# esplash.net
KiCad netlist of a schematic drawn in EAGLE
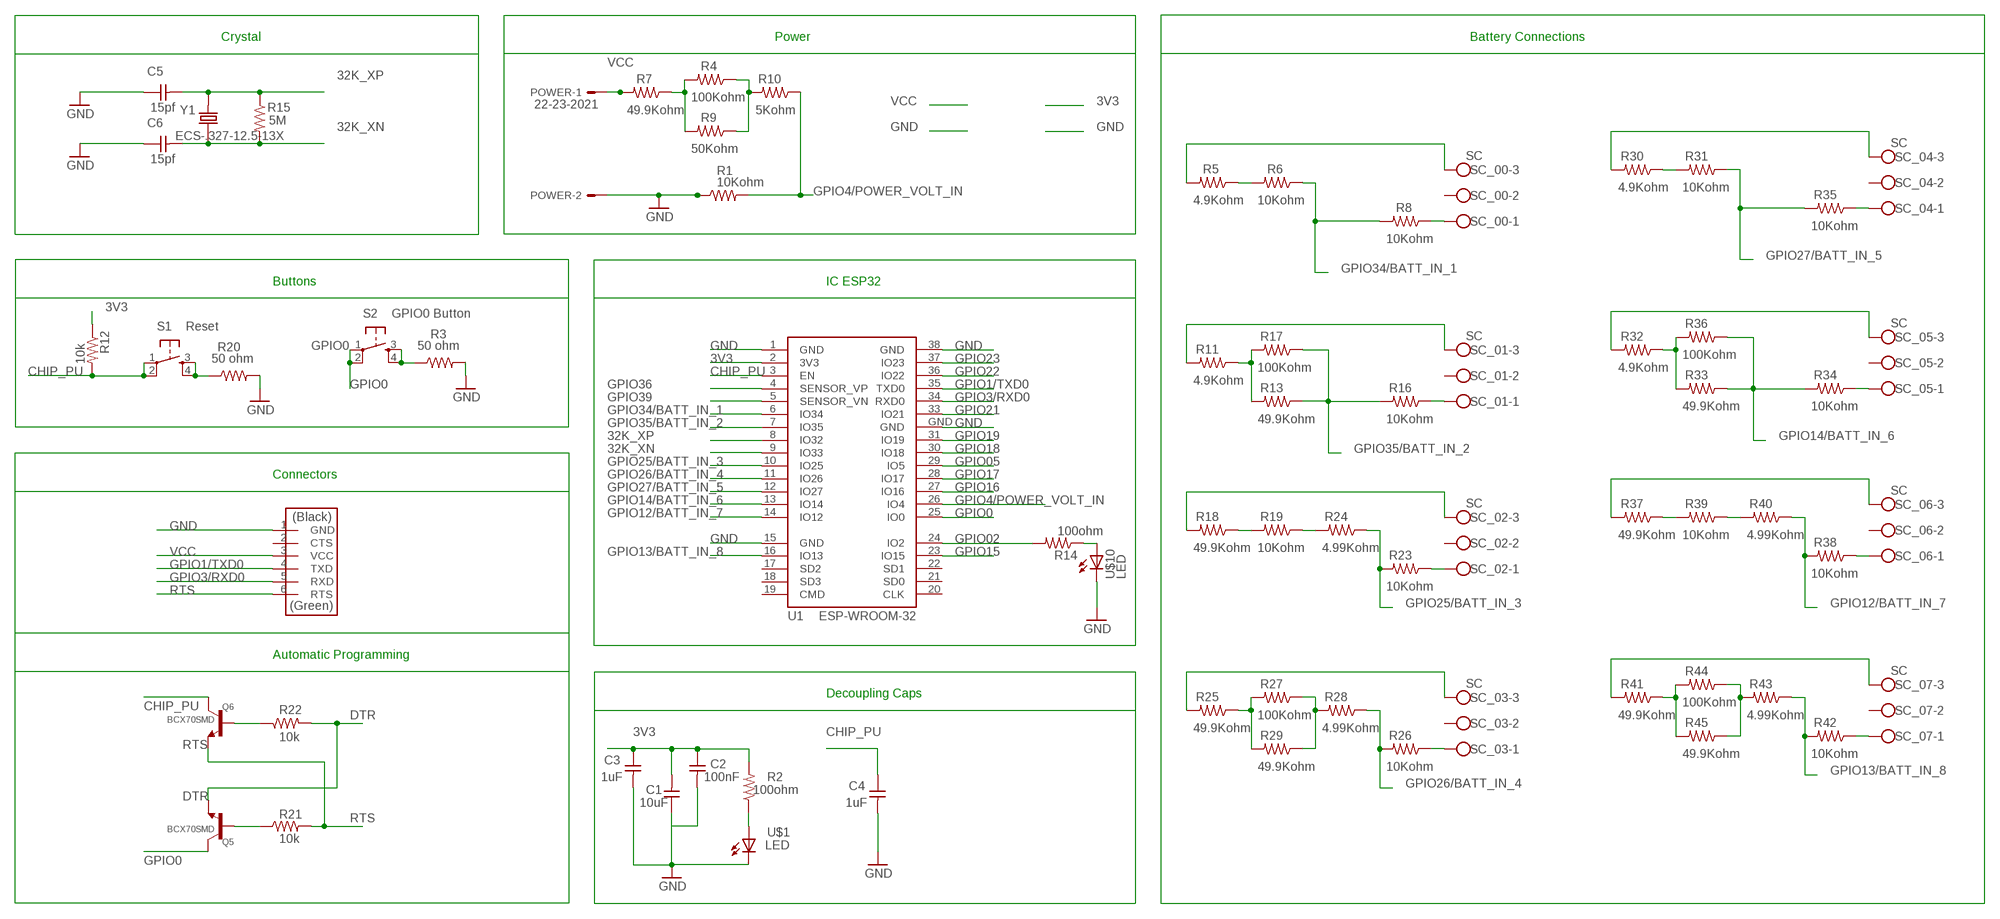
[diagram p0: schematic, sheet 1]

(export (version "E")
  (design (tool "Eeschema 10.0.6"))
  (components
    (comp (ref "C1")
      (value "10uF")
      (footprint "eagle-import:C1206FAB")
      (libsource (lib "eagle-import") (part "CAP-UNPOLARIZEDFAB"))
    )
    (comp (ref "C2")
      (value "100nF")
      (footprint "eagle-import:C1206FAB")
      (libsource (lib "eagle-import") (part "CAP-UNPOLARIZEDFAB"))
    )
    (comp (ref "C3")
      (value "1uF")
      (footprint "eagle-import:C1206FAB")
      (libsource (lib "eagle-import") (part "CAP-UNPOLARIZEDFAB"))
    )
    (comp (ref "C4")
      (value "1uF")
      (footprint "eagle-import:C1206FAB")
      (libsource (lib "eagle-import") (part "CAP-UNPOLARIZEDFAB"))
    )
    (comp (ref "C5")
      (value "15pf")
      (footprint "eagle-import:C1206FAB")
      (libsource (lib "eagle-import") (part "CAP-UNPOLARIZEDFAB"))
    )
    (comp (ref "C6")
      (value "15pf")
      (footprint "eagle-import:C1206FAB")
      (libsource (lib "eagle-import") (part "CAP-UNPOLARIZEDFAB"))
    )
    (comp (ref "POWER")
      (value "22-23-2021")
      (footprint "eagle-import:22-23-2021")
      (fields (field (name "MF") "MOLEX"))
      (libsource (lib "eagle-import") (part "22-23-2021"))
    )
    (comp (ref "Q5")
      (value "BCX70SMD")
      (footprint "eagle-import:SOT23")
      (libsource (lib "eagle-import") (part "BCX70SMD"))
    )
    (comp (ref "Q6")
      (value "BCX70SMD")
      (footprint "eagle-import:SOT23")
      (libsource (lib "eagle-import") (part "BCX70SMD"))
    )
    (comp (ref "R1")
      (value "10Kohm")
      (footprint "eagle-import:R1206FAB")
      (libsource (lib "eagle-import") (part "RES-US1206FAB"))
    )
    (comp (ref "R2")
      (value "100ohm")
      (footprint "eagle-import:R1206")
      (libsource (lib "eagle-import") (part "RES-US1206"))
    )
    (comp (ref "R3")
      (value "50 ohm")
      (footprint "eagle-import:R1206")
      (libsource (lib "eagle-import") (part "RES-US1206"))
    )
    (comp (ref "R4")
      (value "100Kohm")
      (footprint "eagle-import:R1206FAB")
      (libsource (lib "eagle-import") (part "RES-US1206FAB"))
    )
    (comp (ref "R5")
      (value "4.9Kohm")
      (footprint "eagle-import:R1206FAB")
      (libsource (lib "eagle-import") (part "RES-US1206FAB"))
    )
    (comp (ref "R6")
      (value "10Kohm")
      (footprint "eagle-import:R1206FAB")
      (libsource (lib "eagle-import") (part "RES-US1206FAB"))
    )
    (comp (ref "R7")
      (value "49.9Kohm")
      (footprint "eagle-import:R1206FAB")
      (libsource (lib "eagle-import") (part "RES-US1206FAB"))
    )
    (comp (ref "R8")
      (value "10Kohm")
      (footprint "eagle-import:R1206FAB")
      (libsource (lib "eagle-import") (part "RES-US1206FAB"))
    )
    (comp (ref "R9")
      (value "50Kohm")
      (footprint "eagle-import:R1206FAB")
      (libsource (lib "eagle-import") (part "RES-US1206FAB"))
    )
    (comp (ref "R10")
      (value "5Kohm")
      (footprint "eagle-import:R1206FAB")
      (libsource (lib "eagle-import") (part "RES-US1206FAB"))
    )
    (comp (ref "R11")
      (value "4.9Kohm")
      (footprint "eagle-import:R1206FAB")
      (libsource (lib "eagle-import") (part "RES-US1206FAB"))
    )
    (comp (ref "R12")
      (value "10k")
      (footprint "eagle-import:R1206")
      (libsource (lib "eagle-import") (part "RES-US1206"))
    )
    (comp (ref "R13")
      (value "49.9Kohm")
      (footprint "eagle-import:R1206FAB")
      (libsource (lib "eagle-import") (part "RES-US1206FAB"))
    )
    (comp (ref "R14")
      (value "100ohm")
      (footprint "eagle-import:R1206")
      (libsource (lib "eagle-import") (part "RES-US1206"))
    )
    (comp (ref "R15")
      (value "5M")
      (footprint "eagle-import:R1206")
      (libsource (lib "eagle-import") (part "RES-US1206"))
    )
    (comp (ref "R16")
      (value "10Kohm")
      (footprint "eagle-import:R1206FAB")
      (libsource (lib "eagle-import") (part "RES-US1206FAB"))
    )
    (comp (ref "R17")
      (value "100Kohm")
      (footprint "eagle-import:R1206FAB")
      (libsource (lib "eagle-import") (part "RES-US1206FAB"))
    )
    (comp (ref "R18")
      (value "49.9Kohm")
      (footprint "eagle-import:R1206FAB")
      (libsource (lib "eagle-import") (part "RES-US1206FAB"))
    )
    (comp (ref "R19")
      (value "10Kohm")
      (footprint "eagle-import:R1206FAB")
      (libsource (lib "eagle-import") (part "RES-US1206FAB"))
    )
    (comp (ref "R20")
      (value "50 ohm")
      (footprint "eagle-import:R1206")
      (libsource (lib "eagle-import") (part "RES-US1206"))
    )
    (comp (ref "R21")
      (value "10k")
      (footprint "eagle-import:R1206")
      (libsource (lib "eagle-import") (part "RES-US1206"))
    )
    (comp (ref "R22")
      (value "10k")
      (footprint "eagle-import:R1206")
      (libsource (lib "eagle-import") (part "RES-US1206"))
    )
    (comp (ref "R23")
      (value "10Kohm")
      (footprint "eagle-import:R1206FAB")
      (libsource (lib "eagle-import") (part "RES-US1206FAB"))
    )
    (comp (ref "R24")
      (value "4.99Kohm")
      (footprint "eagle-import:R1206FAB")
      (libsource (lib "eagle-import") (part "RES-US1206FAB"))
    )
    (comp (ref "R25")
      (value "49.9Kohm")
      (footprint "eagle-import:R1206FAB")
      (libsource (lib "eagle-import") (part "RES-US1206FAB"))
    )
    (comp (ref "R26")
      (value "10Kohm")
      (footprint "eagle-import:R1206FAB")
      (libsource (lib "eagle-import") (part "RES-US1206FAB"))
    )
    (comp (ref "R27")
      (value "100Kohm")
      (footprint "eagle-import:R1206FAB")
      (libsource (lib "eagle-import") (part "RES-US1206FAB"))
    )
    (comp (ref "R28")
      (value "4.99Kohm")
      (footprint "eagle-import:R1206FAB")
      (libsource (lib "eagle-import") (part "RES-US1206FAB"))
    )
    (comp (ref "R29")
      (value "49.9Kohm")
      (footprint "eagle-import:R1206FAB")
      (libsource (lib "eagle-import") (part "RES-US1206FAB"))
    )
    (comp (ref "R30")
      (value "4.9Kohm")
      (footprint "eagle-import:R1206FAB")
      (libsource (lib "eagle-import") (part "RES-US1206FAB"))
    )
    (comp (ref "R31")
      (value "10Kohm")
      (footprint "eagle-import:R1206FAB")
      (libsource (lib "eagle-import") (part "RES-US1206FAB"))
    )
    (comp (ref "R32")
      (value "4.9Kohm")
      (footprint "eagle-import:R1206FAB")
      (libsource (lib "eagle-import") (part "RES-US1206FAB"))
    )
    (comp (ref "R33")
      (value "49.9Kohm")
      (footprint "eagle-import:R1206FAB")
      (libsource (lib "eagle-import") (part "RES-US1206FAB"))
    )
    (comp (ref "R34")
      (value "10Kohm")
      (footprint "eagle-import:R1206FAB")
      (libsource (lib "eagle-import") (part "RES-US1206FAB"))
    )
    (comp (ref "R35")
      (value "10Kohm")
      (footprint "eagle-import:R1206FAB")
      (libsource (lib "eagle-import") (part "RES-US1206FAB"))
    )
    (comp (ref "R36")
      (value "100Kohm")
      (footprint "eagle-import:R1206FAB")
      (libsource (lib "eagle-import") (part "RES-US1206FAB"))
    )
    (comp (ref "R37")
      (value "49.9Kohm")
      (footprint "eagle-import:R1206FAB")
      (libsource (lib "eagle-import") (part "RES-US1206FAB"))
    )
    (comp (ref "R38")
      (value "10Kohm")
      (footprint "eagle-import:R1206FAB")
      (libsource (lib "eagle-import") (part "RES-US1206FAB"))
    )
    (comp (ref "R39")
      (value "10Kohm")
      (footprint "eagle-import:R1206FAB")
      (libsource (lib "eagle-import") (part "RES-US1206FAB"))
    )
    (comp (ref "R40")
      (value "4.99Kohm")
      (footprint "eagle-import:R1206FAB")
      (libsource (lib "eagle-import") (part "RES-US1206FAB"))
    )
    (comp (ref "R41")
      (value "49.9Kohm")
      (footprint "eagle-import:R1206FAB")
      (libsource (lib "eagle-import") (part "RES-US1206FAB"))
    )
    (comp (ref "R42")
      (value "10Kohm")
      (footprint "eagle-import:R1206FAB")
      (libsource (lib "eagle-import") (part "RES-US1206FAB"))
    )
    (comp (ref "R43")
      (value "4.99Kohm")
      (footprint "eagle-import:R1206FAB")
      (libsource (lib "eagle-import") (part "RES-US1206FAB"))
    )
    (comp (ref "R44")
      (value "100Kohm")
      (footprint "eagle-import:R1206FAB")
      (libsource (lib "eagle-import") (part "RES-US1206FAB"))
    )
    (comp (ref "R45")
      (value "49.9Kohm")
      (footprint "eagle-import:R1206FAB")
      (libsource (lib "eagle-import") (part "RES-US1206FAB"))
    )
    (comp (ref "RTS")
      (value "FTDI-SMD-HEADER")
      (footprint "eagle-import:1X06SMD")
      (libsource (lib "eagle-import") (part "FTDI-SMD-HEADER"))
    )
    (comp (ref "S1")
      (value "Reset")
      (footprint "eagle-import:6MM_SWITCH")
      (libsource (lib "eagle-import") (part "6MM_SWITCH6MM_SWITCH"))
    )
    (comp (ref "S2")
      (value "GPIO0 Button")
      (footprint "eagle-import:6MM_SWITCH")
      (libsource (lib "eagle-import") (part "6MM_SWITCH6MM_SWITCH"))
    )
    (comp (ref "SC_00")
      (value "SC")
      (footprint "eagle-import:W237-103")
      (fields (field (name "MPN") "237-103"))
      (libsource (lib "eagle-import") (part "W237-103"))
    )
    (comp (ref "SC_01")
      (value "SC")
      (footprint "eagle-import:W237-103")
      (fields (field (name "MPN") "237-103"))
      (libsource (lib "eagle-import") (part "W237-103"))
    )
    (comp (ref "SC_02")
      (value "SC")
      (footprint "eagle-import:W237-103")
      (fields (field (name "MPN") "237-103"))
      (libsource (lib "eagle-import") (part "W237-103"))
    )
    (comp (ref "SC_03")
      (value "SC")
      (footprint "eagle-import:W237-103")
      (fields (field (name "MPN") "237-103"))
      (libsource (lib "eagle-import") (part "W237-103"))
    )
    (comp (ref "SC_04")
      (value "SC")
      (footprint "eagle-import:W237-103")
      (fields (field (name "MPN") "237-103"))
      (libsource (lib "eagle-import") (part "W237-103"))
    )
    (comp (ref "SC_05")
      (value "SC")
      (footprint "eagle-import:W237-103")
      (fields (field (name "MPN") "237-103"))
      (libsource (lib "eagle-import") (part "W237-103"))
    )
    (comp (ref "SC_06")
      (value "SC")
      (footprint "eagle-import:W237-103")
      (fields (field (name "MPN") "237-103"))
      (libsource (lib "eagle-import") (part "W237-103"))
    )
    (comp (ref "SC_07")
      (value "SC")
      (footprint "eagle-import:W237-103")
      (fields (field (name "MPN") "237-103"))
      (libsource (lib "eagle-import") (part "W237-103"))
    )
    (comp (ref "U$1")
      (value "LED")
      (footprint "eagle-import:LED1206")
      (libsource (lib "eagle-import") (part "LED"))
    )
    (comp (ref "U$10")
      (value "LED")
      (footprint "eagle-import:LED1206")
      (libsource (lib "eagle-import") (part "LED"))
    )
    (comp (ref "U1")
      (value "ESP-WROOM-32")
      (footprint "eagle-import:ESP-WROOM-32")
      (libsource (lib "eagle-import") (part "ESP-WROOM-32"))
    )
    (comp (ref "Y1")
      (value "ECS-.327-12.5-13X")
      (footprint "eagle-import:XTAL_ECS-.327-12.5-13X")
      (fields (field (name "MF") "ECS Inc."))
      (libsource (lib "eagle-import") (part "ECS-.327-12.5-13X"))
    )
  )
  (nets
    (net (code "1") (name "/3V3") (class "Default")
      (node (ref "C1") (pin "2") (pinfunction "2_2") (pintype "passive"))
      (node (ref "C2") (pin "1") (pinfunction "1_1") (pintype "passive"))
      (node (ref "C3") (pin "1") (pinfunction "1_1") (pintype "passive"))
      (node (ref "R12") (pin "1") (pinfunction "1_1") (pintype "passive"))
      (node (ref "R2") (pin "2") (pinfunction "2_2") (pintype "passive"))
      (node (ref "U1") (pin "2") (pinfunction "3V3_2") (pintype "power_in"))
    )
    (net (code "2") (name "/32K_XN") (class "Default")
      (node (ref "C6") (pin "2") (pinfunction "2_2") (pintype "passive"))
      (node (ref "R15") (pin "2") (pinfunction "2_2") (pintype "passive"))
      (node (ref "U1") (pin "9") (pinfunction "IO33_9") (pintype "bidirectional"))
      (node (ref "Y1") (pin "1") (pinfunction "1_1") (pintype "passive"))
    )
    (net (code "3") (name "/32K_XP") (class "Default")
      (node (ref "C5") (pin "2") (pinfunction "2_2") (pintype "passive"))
      (node (ref "R15") (pin "1") (pinfunction "1_1") (pintype "passive"))
      (node (ref "U1") (pin "8") (pinfunction "IO32_8") (pintype "bidirectional"))
      (node (ref "Y1") (pin "2") (pinfunction "2_2") (pintype "passive"))
    )
    (net (code "4") (name "/CHIP_PU") (class "Default")
      (node (ref "C4") (pin "1") (pinfunction "1_1") (pintype "passive"))
      (node (ref "Q6") (pin "3") (pinfunction "C_3") (pintype "passive"))
      (node (ref "R12") (pin "2") (pinfunction "2_2") (pintype "passive"))
      (node (ref "S1") (pin "1") (pinfunction "P_1") (pintype "passive"))
      (node (ref "S1") (pin "2") (pinfunction "P1_2") (pintype "passive"))
      (node (ref "U1") (pin "3") (pinfunction "EN_3") (pintype "input"))
    )
    (net (code "5") (name "/DTR") (class "Default")
      (node (ref "Q5") (pin "2") (pinfunction "E_2") (pintype "passive"))
      (node (ref "R22") (pin "2") (pinfunction "2_2") (pintype "passive"))
    )
    (net (code "6") (name "/GPIO0") (class "Default")
      (node (ref "Q5") (pin "3") (pinfunction "C_3") (pintype "passive"))
      (node (ref "S2") (pin "1") (pinfunction "P_1") (pintype "passive"))
      (node (ref "S2") (pin "2") (pinfunction "P1_2") (pintype "passive"))
      (node (ref "U1") (pin "25") (pinfunction "IO0_25") (pintype "bidirectional"))
    )
    (net (code "7") (name "/GPIO1{slash}TXD0") (class "Default")
      (node (ref "RTS") (pin "4") (pinfunction "TXD_4") (pintype "bidirectional"))
      (node (ref "U1") (pin "35") (pinfunction "TXD0_35") (pintype "bidirectional"))
    )
    (net (code "8") (name "/GPIO02") (class "Default")
      (node (ref "R14") (pin "2") (pinfunction "2_2") (pintype "passive"))
      (node (ref "U1") (pin "24") (pinfunction "IO2_24") (pintype "bidirectional"))
    )
    (net (code "9") (name "/GPIO3{slash}RXD0") (class "Default")
      (node (ref "RTS") (pin "5") (pinfunction "RXD_5") (pintype "bidirectional"))
      (node (ref "U1") (pin "34") (pinfunction "RXD0_34") (pintype "bidirectional"))
    )
    (net (code "10") (name "/GPIO4{slash}POWER_VOLT_IN") (class "Default")
      (node (ref "R1") (pin "2") (pinfunction "2_2") (pintype "passive"))
      (node (ref "R10") (pin "1") (pinfunction "1_1") (pintype "passive"))
      (node (ref "U1") (pin "26") (pinfunction "IO4_26") (pintype "bidirectional"))
    )
    (net (code "11") (name "/GPIO05") (class "Default")
      (node (ref "U1") (pin "29") (pinfunction "IO5_29") (pintype "bidirectional"))
    )
    (net (code "12") (name "/GPIO12{slash}BATT_IN_7") (class "Default")
      (node (ref "R38") (pin "2") (pinfunction "2_2") (pintype "passive"))
      (node (ref "R40") (pin "1") (pinfunction "1_1") (pintype "passive"))
      (node (ref "U1") (pin "14") (pinfunction "IO12_14") (pintype "bidirectional"))
    )
    (net (code "13") (name "/GPIO13{slash}BATT_IN_8") (class "Default")
      (node (ref "R42") (pin "2") (pinfunction "2_2") (pintype "passive"))
      (node (ref "R43") (pin "1") (pinfunction "1_1") (pintype "passive"))
      (node (ref "U1") (pin "16") (pinfunction "IO13_16") (pintype "bidirectional"))
    )
    (net (code "14") (name "/GPIO14{slash}BATT_IN_6") (class "Default")
      (node (ref "R33") (pin "1") (pinfunction "1_1") (pintype "passive"))
      (node (ref "R34") (pin "2") (pinfunction "2_2") (pintype "passive"))
      (node (ref "R36") (pin "1") (pinfunction "1_1") (pintype "passive"))
      (node (ref "U1") (pin "13") (pinfunction "IO14_13") (pintype "bidirectional"))
    )
    (net (code "15") (name "/GPIO15") (class "Default")
      (node (ref "U1") (pin "23") (pinfunction "IO15_23") (pintype "bidirectional"))
    )
    (net (code "16") (name "/GPIO16") (class "Default")
      (node (ref "U1") (pin "27") (pinfunction "IO16_27") (pintype "bidirectional"))
    )
    (net (code "17") (name "/GPIO17") (class "Default")
      (node (ref "U1") (pin "28") (pinfunction "IO17_28") (pintype "bidirectional"))
    )
    (net (code "18") (name "/GPIO18") (class "Default")
      (node (ref "U1") (pin "30") (pinfunction "IO18_30") (pintype "bidirectional"))
    )
    (net (code "19") (name "/GPIO19") (class "Default")
      (node (ref "U1") (pin "31") (pinfunction "IO19_31") (pintype "bidirectional"))
    )
    (net (code "20") (name "/GPIO21") (class "Default")
      (node (ref "U1") (pin "33") (pinfunction "IO21_33") (pintype "bidirectional"))
    )
    (net (code "21") (name "/GPIO22") (class "Default")
      (node (ref "U1") (pin "36") (pinfunction "IO22_36") (pintype "bidirectional"))
    )
    (net (code "22") (name "/GPIO23") (class "Default")
      (node (ref "U1") (pin "37") (pinfunction "IO23_37") (pintype "bidirectional"))
    )
    (net (code "23") (name "/GPIO25{slash}BATT_IN_3") (class "Default")
      (node (ref "R23") (pin "2") (pinfunction "2_2") (pintype "passive"))
      (node (ref "R24") (pin "1") (pinfunction "1_1") (pintype "passive"))
      (node (ref "U1") (pin "10") (pinfunction "IO25_10") (pintype "bidirectional"))
    )
    (net (code "24") (name "/GPIO26{slash}BATT_IN_4") (class "Default")
      (node (ref "R26") (pin "2") (pinfunction "2_2") (pintype "passive"))
      (node (ref "R28") (pin "1") (pinfunction "1_1") (pintype "passive"))
      (node (ref "U1") (pin "11") (pinfunction "IO26_11") (pintype "bidirectional"))
    )
    (net (code "25") (name "/GPIO27{slash}BATT_IN_5") (class "Default")
      (node (ref "R31") (pin "1") (pinfunction "1_1") (pintype "passive"))
      (node (ref "R35") (pin "2") (pinfunction "2_2") (pintype "passive"))
      (node (ref "U1") (pin "12") (pinfunction "IO27_12") (pintype "bidirectional"))
    )
    (net (code "26") (name "/GPIO34{slash}BATT_IN_1") (class "Default")
      (node (ref "R6") (pin "1") (pinfunction "1_1") (pintype "passive"))
      (node (ref "R8") (pin "2") (pinfunction "2_2") (pintype "passive"))
      (node (ref "U1") (pin "6") (pinfunction "IO34_6") (pintype "bidirectional"))
    )
    (net (code "27") (name "/GPIO35{slash}BATT_IN_2") (class "Default")
      (node (ref "R13") (pin "1") (pinfunction "1_1") (pintype "passive"))
      (node (ref "R16") (pin "2") (pinfunction "2_2") (pintype "passive"))
      (node (ref "R17") (pin "1") (pinfunction "1_1") (pintype "passive"))
      (node (ref "U1") (pin "7") (pinfunction "IO35_7") (pintype "bidirectional"))
    )
    (net (code "28") (name "/GPIO36") (class "Default")
      (node (ref "U1") (pin "4") (pinfunction "SENSOR_VP_4") (pintype "bidirectional"))
    )
    (net (code "29") (name "/GPIO39") (class "Default")
      (node (ref "U1") (pin "5") (pinfunction "SENSOR_VN_5") (pintype "bidirectional"))
    )
    (net (code "31") (name "/RTS") (class "Default")
      (node (ref "Q6") (pin "2") (pinfunction "E_2") (pintype "passive"))
      (node (ref "R21") (pin "2") (pinfunction "2_2") (pintype "passive"))
      (node (ref "RTS") (pin "6") (pinfunction "RTS_6") (pintype "bidirectional"))
    )
    (net (code "32") (name "/VCC") (class "Default")
      (node (ref "POWER") (pin "1") (pinfunction "S_1") (pintype "passive"))
      (node (ref "R7") (pin "2") (pinfunction "2_2") (pintype "passive"))
      (node (ref "RTS") (pin "3") (pinfunction "VCC_3") (pintype "bidirectional"))
    )
    (net (code "33") (name "GND") (class "Default")
      (node (ref "C1") (pin "1") (pinfunction "1_1") (pintype "passive"))
      (node (ref "C2") (pin "2") (pinfunction "2_2") (pintype "passive"))
      (node (ref "C3") (pin "2") (pinfunction "2_2") (pintype "passive"))
      (node (ref "C4") (pin "2") (pinfunction "2_2") (pintype "passive"))
      (node (ref "C5") (pin "1") (pinfunction "1_1") (pintype "passive"))
      (node (ref "C6") (pin "1") (pinfunction "1_1") (pintype "passive"))
      (node (ref "POWER") (pin "2") (pinfunction "S_2") (pintype "passive"))
      (node (ref "R1") (pin "1") (pinfunction "1_1") (pintype "passive"))
      (node (ref "R20") (pin "2") (pinfunction "2_2") (pintype "passive"))
      (node (ref "R3") (pin "2") (pinfunction "2_2") (pintype "passive"))
      (node (ref "RTS") (pin "1") (pinfunction "GND_1") (pintype "bidirectional"))
      (node (ref "U$1") (pin "2") (pinfunction "C_2") (pintype "passive"))
      (node (ref "U$10") (pin "2") (pinfunction "C_2") (pintype "passive"))
      (node (ref "U1") (pin "1") (pinfunction "GND_1") (pintype "power_in"))
      (node (ref "U1") (pin "15") (pinfunction "GND_15") (pintype "power_in"))
      (node (ref "U1") (pin "38") (pinfunction "GND_38") (pintype "power_in"))
      (node (ref "U1") (pin "GND") (pinfunction "GND_GND") (pintype "power_in"))
    )
    (net (code "34") (name "Net-(Q5-B)") (class "Default")
      (node (ref "Q5") (pin "1") (pinfunction "B_1") (pintype "passive"))
      (node (ref "R21") (pin "1") (pinfunction "1_1") (pintype "passive"))
    )
    (net (code "35") (name "Net-(Q6-B)") (class "Default")
      (node (ref "Q6") (pin "1") (pinfunction "B_1") (pintype "passive"))
      (node (ref "R22") (pin "1") (pinfunction "1_1") (pintype "passive"))
    )
    (net (code "36") (name "Net-(R4-Pad2)") (class "Default")
      (node (ref "R4") (pin "2") (pinfunction "2_2") (pintype "passive"))
      (node (ref "R7") (pin "1") (pinfunction "1_1") (pintype "passive"))
      (node (ref "R9") (pin "2") (pinfunction "2_2") (pintype "passive"))
    )
    (net (code "37") (name "Net-(R5-Pad1)") (class "Default")
      (node (ref "R5") (pin "1") (pinfunction "1_1") (pintype "passive"))
      (node (ref "R6") (pin "2") (pinfunction "2_2") (pintype "passive"))
    )
    (net (code "38") (name "Net-(R10-Pad2)") (class "Default")
      (node (ref "R10") (pin "2") (pinfunction "2_2") (pintype "passive"))
      (node (ref "R4") (pin "1") (pinfunction "1_1") (pintype "passive"))
      (node (ref "R9") (pin "1") (pinfunction "1_1") (pintype "passive"))
    )
    (net (code "39") (name "Net-(R11-Pad1)") (class "Default")
      (node (ref "R11") (pin "1") (pinfunction "1_1") (pintype "passive"))
      (node (ref "R13") (pin "2") (pinfunction "2_2") (pintype "passive"))
      (node (ref "R17") (pin "2") (pinfunction "2_2") (pintype "passive"))
    )
    (net (code "40") (name "Net-(R18-Pad1)") (class "Default")
      (node (ref "R18") (pin "1") (pinfunction "1_1") (pintype "passive"))
      (node (ref "R19") (pin "2") (pinfunction "2_2") (pintype "passive"))
    )
    (net (code "41") (name "Net-(R19-Pad1)") (class "Default")
      (node (ref "R19") (pin "1") (pinfunction "1_1") (pintype "passive"))
      (node (ref "R24") (pin "2") (pinfunction "2_2") (pintype "passive"))
    )
    (net (code "42") (name "Net-(R25-Pad1)") (class "Default")
      (node (ref "R25") (pin "1") (pinfunction "1_1") (pintype "passive"))
      (node (ref "R27") (pin "2") (pinfunction "2_2") (pintype "passive"))
      (node (ref "R29") (pin "2") (pinfunction "2_2") (pintype "passive"))
    )
    (net (code "43") (name "Net-(R27-Pad1)") (class "Default")
      (node (ref "R27") (pin "1") (pinfunction "1_1") (pintype "passive"))
      (node (ref "R28") (pin "2") (pinfunction "2_2") (pintype "passive"))
      (node (ref "R29") (pin "1") (pinfunction "1_1") (pintype "passive"))
    )
    (net (code "44") (name "Net-(R30-Pad1)") (class "Default")
      (node (ref "R30") (pin "1") (pinfunction "1_1") (pintype "passive"))
      (node (ref "R31") (pin "2") (pinfunction "2_2") (pintype "passive"))
    )
    (net (code "45") (name "Net-(R32-Pad1)") (class "Default")
      (node (ref "R32") (pin "1") (pinfunction "1_1") (pintype "passive"))
      (node (ref "R33") (pin "2") (pinfunction "2_2") (pintype "passive"))
      (node (ref "R36") (pin "2") (pinfunction "2_2") (pintype "passive"))
    )
    (net (code "46") (name "Net-(R37-Pad1)") (class "Default")
      (node (ref "R37") (pin "1") (pinfunction "1_1") (pintype "passive"))
      (node (ref "R39") (pin "2") (pinfunction "2_2") (pintype "passive"))
    )
    (net (code "47") (name "Net-(R39-Pad1)") (class "Default")
      (node (ref "R39") (pin "1") (pinfunction "1_1") (pintype "passive"))
      (node (ref "R40") (pin "2") (pinfunction "2_2") (pintype "passive"))
    )
    (net (code "48") (name "Net-(R41-Pad1)") (class "Default")
      (node (ref "R41") (pin "1") (pinfunction "1_1") (pintype "passive"))
      (node (ref "R44") (pin "2") (pinfunction "2_2") (pintype "passive"))
      (node (ref "R45") (pin "2") (pinfunction "2_2") (pintype "passive"))
    )
    (net (code "49") (name "Net-(R43-Pad2)") (class "Default")
      (node (ref "R43") (pin "2") (pinfunction "2_2") (pintype "passive"))
      (node (ref "R44") (pin "1") (pinfunction "1_1") (pintype "passive"))
      (node (ref "R45") (pin "1") (pinfunction "1_1") (pintype "passive"))
    )
    (net (code "50") (name "Net-(S1-S)") (class "Default")
      (node (ref "R20") (pin "1") (pinfunction "1_1") (pintype "passive"))
      (node (ref "S1") (pin "3") (pinfunction "S_3") (pintype "passive"))
      (node (ref "S1") (pin "4") (pinfunction "S1_4") (pintype "passive"))
    )
    (net (code "51") (name "Net-(S2-S)") (class "Default")
      (node (ref "R3") (pin "1") (pinfunction "1_1") (pintype "passive"))
      (node (ref "S2") (pin "3") (pinfunction "S_3") (pintype "passive"))
      (node (ref "S2") (pin "4") (pinfunction "S1_4") (pintype "passive"))
    )
    (net (code "52") (name "Net-(SC_00A-KL)") (class "Default")
      (node (ref "R8") (pin "1") (pinfunction "1_1") (pintype "passive"))
      (node (ref "SC_00") (pin "1") (pinfunction "KL_1") (pintype "passive"))
    )
    (net (code "53") (name "Net-(SC_00C-KL)") (class "Default")
      (node (ref "R5") (pin "2") (pinfunction "2_2") (pintype "passive"))
      (node (ref "SC_00") (pin "3") (pinfunction "KL_3") (pintype "passive"))
    )
    (net (code "54") (name "Net-(SC_01A-KL)") (class "Default")
      (node (ref "R16") (pin "1") (pinfunction "1_1") (pintype "passive"))
      (node (ref "SC_01") (pin "1") (pinfunction "KL_1") (pintype "passive"))
    )
    (net (code "55") (name "Net-(SC_01C-KL)") (class "Default")
      (node (ref "R11") (pin "2") (pinfunction "2_2") (pintype "passive"))
      (node (ref "SC_01") (pin "3") (pinfunction "KL_3") (pintype "passive"))
    )
    (net (code "56") (name "Net-(SC_02A-KL)") (class "Default")
      (node (ref "R23") (pin "1") (pinfunction "1_1") (pintype "passive"))
      (node (ref "SC_02") (pin "1") (pinfunction "KL_1") (pintype "passive"))
    )
    (net (code "57") (name "Net-(SC_02C-KL)") (class "Default")
      (node (ref "R18") (pin "2") (pinfunction "2_2") (pintype "passive"))
      (node (ref "SC_02") (pin "3") (pinfunction "KL_3") (pintype "passive"))
    )
    (net (code "58") (name "Net-(SC_03A-KL)") (class "Default")
      (node (ref "R26") (pin "1") (pinfunction "1_1") (pintype "passive"))
      (node (ref "SC_03") (pin "1") (pinfunction "KL_1") (pintype "passive"))
    )
    (net (code "59") (name "Net-(SC_03C-KL)") (class "Default")
      (node (ref "R25") (pin "2") (pinfunction "2_2") (pintype "passive"))
      (node (ref "SC_03") (pin "3") (pinfunction "KL_3") (pintype "passive"))
    )
    (net (code "60") (name "Net-(SC_04A-KL)") (class "Default")
      (node (ref "R35") (pin "1") (pinfunction "1_1") (pintype "passive"))
      (node (ref "SC_04") (pin "1") (pinfunction "KL_1") (pintype "passive"))
    )
    (net (code "61") (name "Net-(SC_04C-KL)") (class "Default")
      (node (ref "R30") (pin "2") (pinfunction "2_2") (pintype "passive"))
      (node (ref "SC_04") (pin "3") (pinfunction "KL_3") (pintype "passive"))
    )
    (net (code "62") (name "Net-(SC_05A-KL)") (class "Default")
      (node (ref "R34") (pin "1") (pinfunction "1_1") (pintype "passive"))
      (node (ref "SC_05") (pin "1") (pinfunction "KL_1") (pintype "passive"))
    )
    (net (code "63") (name "Net-(SC_05C-KL)") (class "Default")
      (node (ref "R32") (pin "2") (pinfunction "2_2") (pintype "passive"))
      (node (ref "SC_05") (pin "3") (pinfunction "KL_3") (pintype "passive"))
    )
    (net (code "64") (name "Net-(SC_06A-KL)") (class "Default")
      (node (ref "R38") (pin "1") (pinfunction "1_1") (pintype "passive"))
      (node (ref "SC_06") (pin "1") (pinfunction "KL_1") (pintype "passive"))
    )
    (net (code "65") (name "Net-(SC_06C-KL)") (class "Default")
      (node (ref "R37") (pin "2") (pinfunction "2_2") (pintype "passive"))
      (node (ref "SC_06") (pin "3") (pinfunction "KL_3") (pintype "passive"))
    )
    (net (code "66") (name "Net-(SC_07A-KL)") (class "Default")
      (node (ref "R42") (pin "1") (pinfunction "1_1") (pintype "passive"))
      (node (ref "SC_07") (pin "1") (pinfunction "KL_1") (pintype "passive"))
    )
    (net (code "67") (name "Net-(SC_07C-KL)") (class "Default")
      (node (ref "R41") (pin "2") (pinfunction "2_2") (pintype "passive"))
      (node (ref "SC_07") (pin "3") (pinfunction "KL_3") (pintype "passive"))
    )
    (net (code "68") (name "Net-(U$1-A)") (class "Default")
      (node (ref "R2") (pin "1") (pinfunction "1_1") (pintype "passive"))
      (node (ref "U$1") (pin "1") (pinfunction "A_1") (pintype "passive"))
    )
    (net (code "69") (name "Net-(U$10-A)") (class "Default")
      (node (ref "R14") (pin "1") (pinfunction "1_1") (pintype "passive"))
      (node (ref "U$10") (pin "1") (pinfunction "A_1") (pintype "passive"))
    )
    (net (code "70") (name "unconnected-(RTS-CTS-Pad2)") (class "Default")
      (node (ref "RTS") (pin "2") (pinfunction "CTS_2") (pintype "bidirectional"))
    )
    (net (code "71") (name "unconnected-(SC_00B-KL-Pad2)") (class "Default")
      (node (ref "SC_00") (pin "2") (pinfunction "KL_2") (pintype "passive"))
    )
    (net (code "72") (name "unconnected-(SC_01B-KL-Pad2)") (class "Default")
      (node (ref "SC_01") (pin "2") (pinfunction "KL_2") (pintype "passive"))
    )
    (net (code "73") (name "unconnected-(SC_02B-KL-Pad2)") (class "Default")
      (node (ref "SC_02") (pin "2") (pinfunction "KL_2") (pintype "passive"))
    )
    (net (code "74") (name "unconnected-(SC_03B-KL-Pad2)") (class "Default")
      (node (ref "SC_03") (pin "2") (pinfunction "KL_2") (pintype "passive"))
    )
    (net (code "75") (name "unconnected-(SC_04B-KL-Pad2)") (class "Default")
      (node (ref "SC_04") (pin "2") (pinfunction "KL_2") (pintype "passive"))
    )
    (net (code "76") (name "unconnected-(SC_05B-KL-Pad2)") (class "Default")
      (node (ref "SC_05") (pin "2") (pinfunction "KL_2") (pintype "passive"))
    )
    (net (code "77") (name "unconnected-(SC_06B-KL-Pad2)") (class "Default")
      (node (ref "SC_06") (pin "2") (pinfunction "KL_2") (pintype "passive"))
    )
    (net (code "78") (name "unconnected-(SC_07B-KL-Pad2)") (class "Default")
      (node (ref "SC_07") (pin "2") (pinfunction "KL_2") (pintype "passive"))
    )
    (net (code "79") (name "unconnected-(U1-CLK-Pad20)") (class "Default")
      (node (ref "U1") (pin "20") (pinfunction "CLK_20") (pintype "bidirectional"))
    )
    (net (code "80") (name "unconnected-(U1-CMD-Pad19)") (class "Default")
      (node (ref "U1") (pin "19") (pinfunction "CMD_19") (pintype "bidirectional"))
    )
    (net (code "81") (name "unconnected-(U1-SD0-Pad21)") (class "Default")
      (node (ref "U1") (pin "21") (pinfunction "SD0_21") (pintype "bidirectional"))
    )
    (net (code "82") (name "unconnected-(U1-SD1-Pad22)") (class "Default")
      (node (ref "U1") (pin "22") (pinfunction "SD1_22") (pintype "bidirectional"))
    )
    (net (code "83") (name "unconnected-(U1-SD2-Pad17)") (class "Default")
      (node (ref "U1") (pin "17") (pinfunction "SD2_17") (pintype "bidirectional"))
    )
    (net (code "84") (name "unconnected-(U1-SD3-Pad18)") (class "Default")
      (node (ref "U1") (pin "18") (pinfunction "SD3_18") (pintype "bidirectional"))
    )
  )
)
